# prototype2.net
KiCad netlist of a schematic drawn in EAGLE
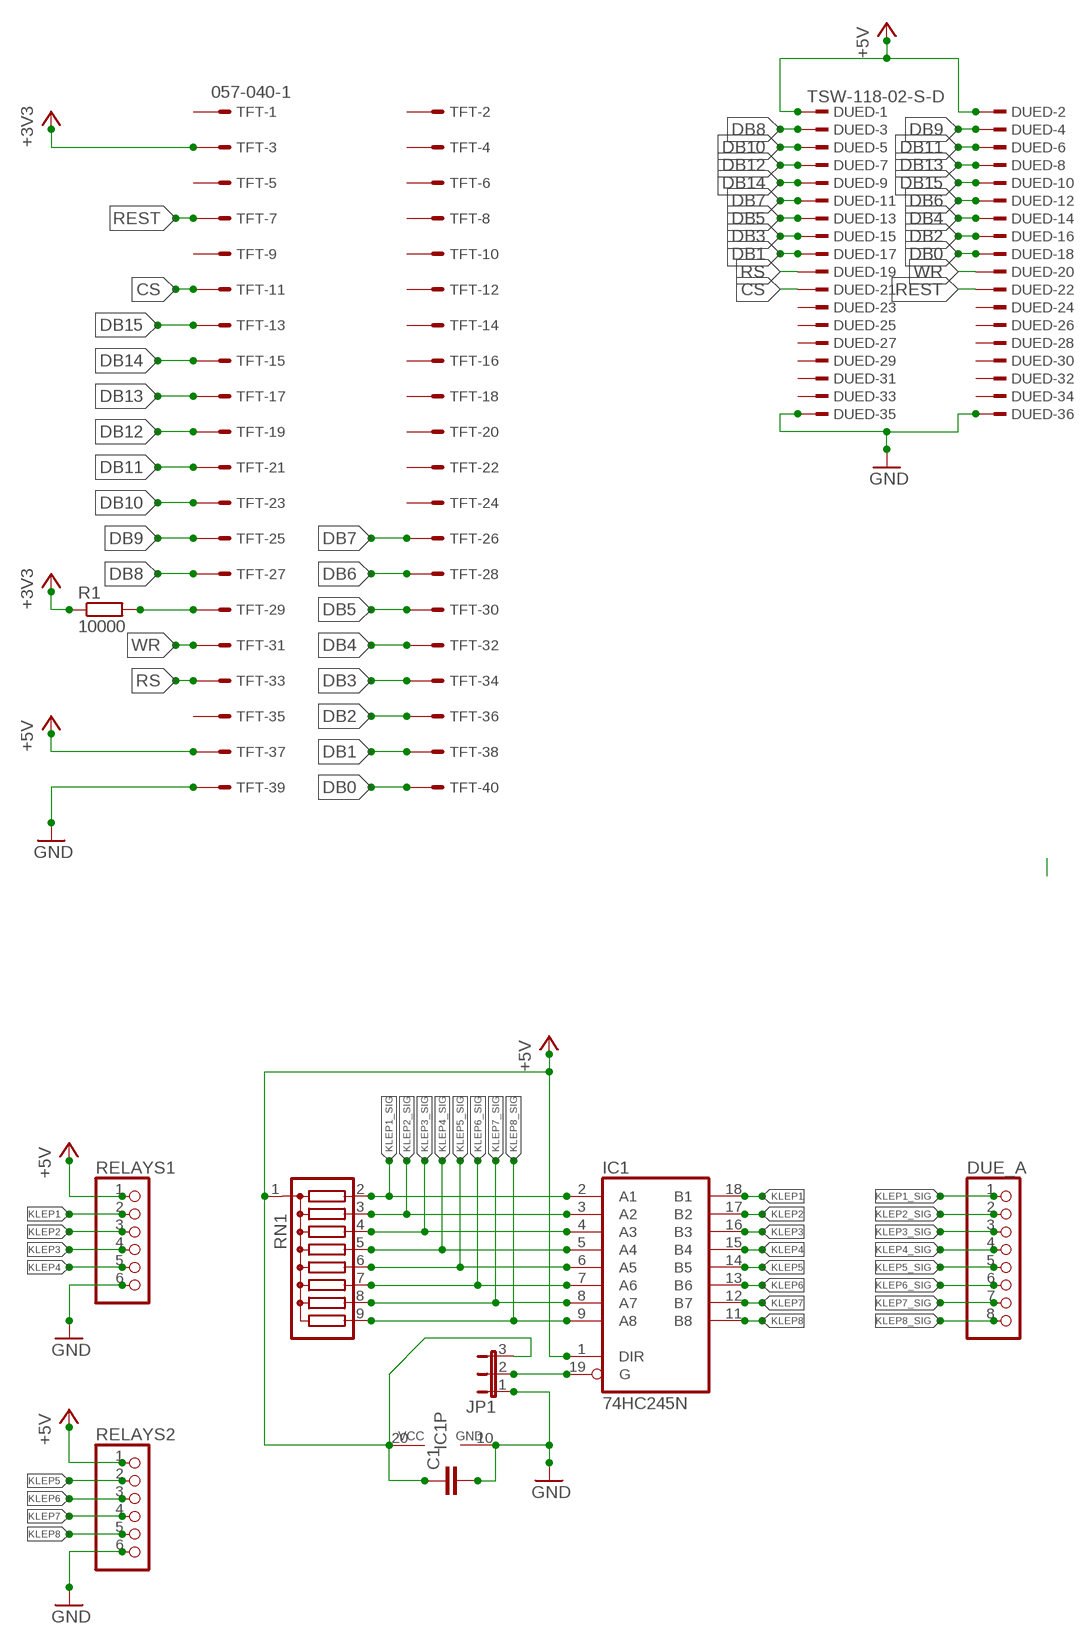
[diagram p0: schematic, sheet 1, part 1 of 2]
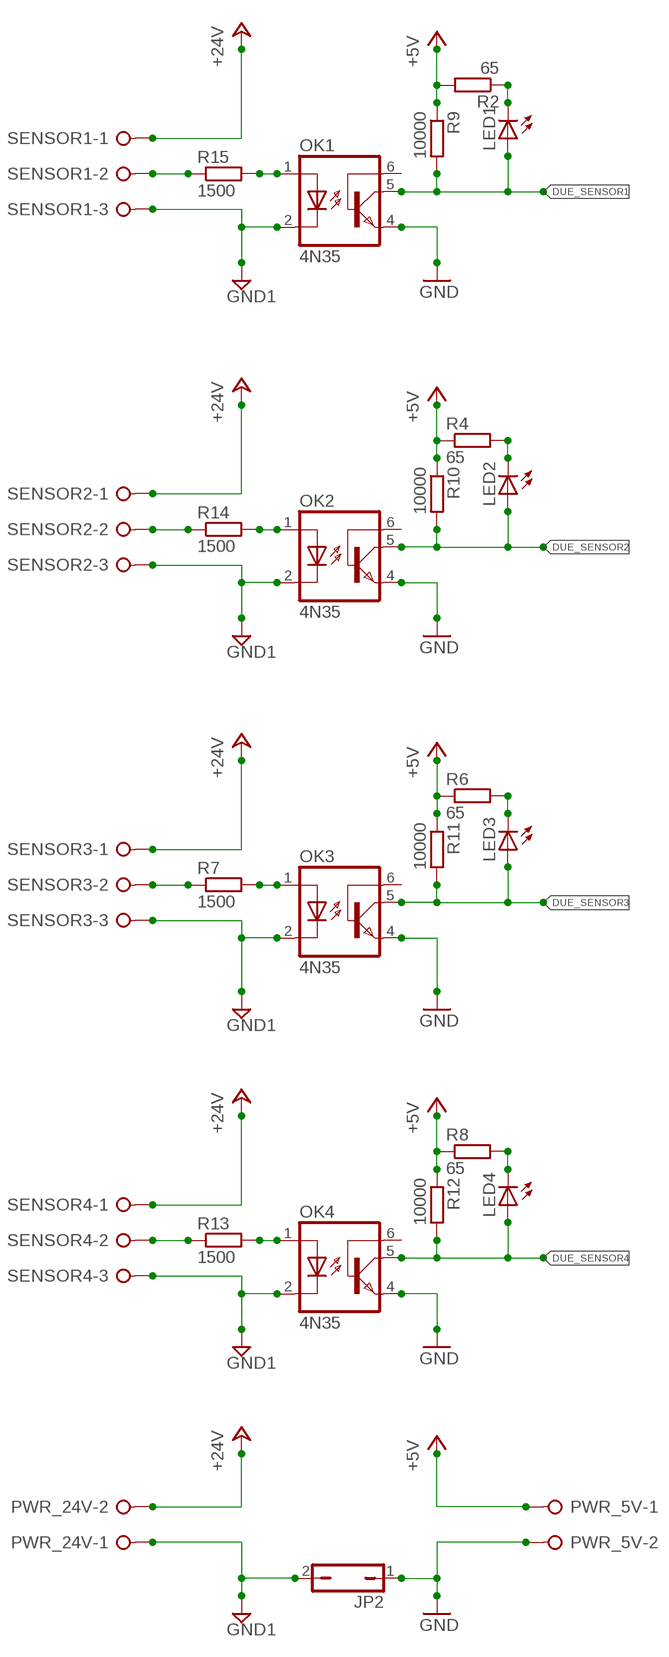
[diagram p1: schematic, sheet 1, part 2 of 2]

(export (version "E")
  (design (tool "Eeschema 10.0.6"))
  (components
    (comp (ref "C1")
      (value "C-EU025-024X044")
      (footprint "eagle-import:C025-024X044")
      (libsource (lib "eagle-import") (part "C-EU025-024X044"))
    )
    (comp (ref "DUED")
      (value "TSW-118-02-S-D")
      (footprint "eagle-import:TSW-118-02-S-D")
      (libsource (lib "eagle-import") (part "TSW-118-02-S-D"))
    )
    (comp (ref "DUE_A")
      (value "PINHD-1X8")
      (footprint "eagle-import:1X08")
      (libsource (lib "eagle-import") (part "PINHD-1X8"))
    )
    (comp (ref "IC1")
      (value "74HC245N")
      (footprint "eagle-import:DIL20")
      (libsource (lib "eagle-import") (part "74245NHC"))
    )
    (comp (ref "JP1")
      (value "JP2E")
      (footprint "eagle-import:JP2")
      (libsource (lib "eagle-import") (part "JP2E"))
    )
    (comp (ref "JP2")
      (value "JP1Q")
      (footprint "eagle-import:JP1")
      (libsource (lib "eagle-import") (part "JP1Q"))
    )
    (comp (ref "LED1")
      (value "LED5MM")
      (footprint "eagle-import:LED5MM")
      (libsource (lib "eagle-import") (part "LED5MM"))
    )
    (comp (ref "LED2")
      (value "LED5MM")
      (footprint "eagle-import:LED5MM")
      (libsource (lib "eagle-import") (part "LED5MM"))
    )
    (comp (ref "LED3")
      (value "LED5MM")
      (footprint "eagle-import:LED5MM")
      (libsource (lib "eagle-import") (part "LED5MM"))
    )
    (comp (ref "LED4")
      (value "LED5MM")
      (footprint "eagle-import:LED5MM")
      (libsource (lib "eagle-import") (part "LED5MM"))
    )
    (comp (ref "OK1")
      (value "4N35")
      (footprint "eagle-import:DIL06")
      (fields (field (name "MF") "FAIRCHILD SEMICONDUCTOR"))
      (libsource (lib "eagle-import") (part "4N35"))
    )
    (comp (ref "OK2")
      (value "4N35")
      (footprint "eagle-import:DIL06")
      (fields (field (name "MF") "FAIRCHILD SEMICONDUCTOR"))
      (libsource (lib "eagle-import") (part "4N35"))
    )
    (comp (ref "OK3")
      (value "4N35")
      (footprint "eagle-import:DIL06")
      (fields (field (name "MF") "FAIRCHILD SEMICONDUCTOR"))
      (libsource (lib "eagle-import") (part "4N35"))
    )
    (comp (ref "OK4")
      (value "4N35")
      (footprint "eagle-import:DIL06")
      (fields (field (name "MF") "FAIRCHILD SEMICONDUCTOR"))
      (libsource (lib "eagle-import") (part "4N35"))
    )
    (comp (ref "PWR_5V")
      (value "W237-02P")
      (footprint "eagle-import:W237-132")
      (libsource (lib "eagle-import") (part "W237-02P"))
    )
    (comp (ref "PWR_24V")
      (value "W237-02P")
      (footprint "eagle-import:W237-132")
      (libsource (lib "eagle-import") (part "W237-02P"))
    )
    (comp (ref "R1")
      (value "10000")
      (footprint "eagle-import:0204_5")
      (libsource (lib "eagle-import") (part "R-EU_0204/5"))
    )
    (comp (ref "R2")
      (value "65")
      (footprint "eagle-import:0204_5")
      (libsource (lib "eagle-import") (part "R-EU_0204/5"))
    )
    (comp (ref "R4")
      (value "65")
      (footprint "eagle-import:0204_5")
      (libsource (lib "eagle-import") (part "R-EU_0204/5"))
    )
    (comp (ref "R6")
      (value "65")
      (footprint "eagle-import:0204_5")
      (libsource (lib "eagle-import") (part "R-EU_0204/5"))
    )
    (comp (ref "R7")
      (value "1500")
      (footprint "eagle-import:0204_5")
      (libsource (lib "eagle-import") (part "R-EU_0204/5"))
    )
    (comp (ref "R8")
      (value "65")
      (footprint "eagle-import:0204_5")
      (libsource (lib "eagle-import") (part "R-EU_0204/5"))
    )
    (comp (ref "R9")
      (value "10000")
      (footprint "eagle-import:0204_5")
      (libsource (lib "eagle-import") (part "R-EU_0204/5"))
    )
    (comp (ref "R10")
      (value "10000")
      (footprint "eagle-import:0204_5")
      (libsource (lib "eagle-import") (part "R-EU_0204/5"))
    )
    (comp (ref "R11")
      (value "10000")
      (footprint "eagle-import:0204_5")
      (libsource (lib "eagle-import") (part "R-EU_0204/5"))
    )
    (comp (ref "R12")
      (value "10000")
      (footprint "eagle-import:0204_5")
      (libsource (lib "eagle-import") (part "R-EU_0204/5"))
    )
    (comp (ref "R13")
      (value "1500")
      (footprint "eagle-import:0204_5")
      (libsource (lib "eagle-import") (part "R-EU_0204/5"))
    )
    (comp (ref "R14")
      (value "1500")
      (footprint "eagle-import:0204_5")
      (libsource (lib "eagle-import") (part "R-EU_0204/5"))
    )
    (comp (ref "R15")
      (value "1500")
      (footprint "eagle-import:0204_5")
      (libsource (lib "eagle-import") (part "R-EU_0204/5"))
    )
    (comp (ref "RELAYS1")
      (value "PINHD-1X6")
      (footprint "eagle-import:1X06")
      (libsource (lib "eagle-import") (part "PINHD-1X6"))
    )
    (comp (ref "RELAYS2")
      (value "PINHD-1X6")
      (footprint "eagle-import:1X06")
      (libsource (lib "eagle-import") (part "PINHD-1X6"))
    )
    (comp (ref "RN1")
      (value "G08R")
      (footprint "eagle-import:SIL9")
      (libsource (lib "eagle-import") (part "G08R"))
    )
    (comp (ref "SENSOR1")
      (value "W237-03P")
      (footprint "eagle-import:W237-133")
      (libsource (lib "eagle-import") (part "W237-03P"))
    )
    (comp (ref "SENSOR2")
      (value "W237-03P")
      (footprint "eagle-import:W237-133")
      (libsource (lib "eagle-import") (part "W237-03P"))
    )
    (comp (ref "SENSOR3")
      (value "W237-03P")
      (footprint "eagle-import:W237-133")
      (libsource (lib "eagle-import") (part "W237-03P"))
    )
    (comp (ref "SENSOR4")
      (value "W237-03P")
      (footprint "eagle-import:W237-133")
      (libsource (lib "eagle-import") (part "W237-03P"))
    )
    (comp (ref "TFT")
      (value "057-040-1")
      (footprint "eagle-import:057-040-1")
      (libsource (lib "eagle-import") (part "057-040-1"))
    )
  )
  (nets
    (net (code "1") (name "+3V3") (class "Default")
      (node (ref "R1") (pin "1") (pinfunction "1_1") (pintype "passive"))
      (node (ref "TFT") (pin "3") (pinfunction "S_3") (pintype "passive"))
    )
    (net (code "2") (name "+5V") (class "Default")
      (node (ref "C1") (pin "1") (pinfunction "1_1") (pintype "passive"))
      (node (ref "DUED") (pin "1") (pinfunction "1_1") (pintype "passive"))
      (node (ref "DUED") (pin "2") (pinfunction "1_2") (pintype "passive"))
      (node (ref "IC1") (pin "1") (pinfunction "DIR_1") (pintype "input"))
      (node (ref "IC1") (pin "20") (pinfunction "VCC_20") (pintype "power_in"))
      (node (ref "JP1") (pin "3") (pinfunction "3_3") (pintype "passive"))
      (node (ref "PWR_5V") (pin "1") (pinfunction "KL_1") (pintype "passive"))
      (node (ref "R10") (pin "1") (pinfunction "1_1") (pintype "passive"))
      (node (ref "R11") (pin "1") (pinfunction "1_1") (pintype "passive"))
      (node (ref "R12") (pin "1") (pinfunction "1_1") (pintype "passive"))
      (node (ref "R2") (pin "2") (pinfunction "2_2") (pintype "passive"))
      (node (ref "R4") (pin "1") (pinfunction "1_1") (pintype "passive"))
      (node (ref "R6") (pin "1") (pinfunction "1_1") (pintype "passive"))
      (node (ref "R8") (pin "1") (pinfunction "1_1") (pintype "passive"))
      (node (ref "R9") (pin "1") (pinfunction "1_1") (pintype "passive"))
      (node (ref "RELAYS1") (pin "1") (pinfunction "1_1") (pintype "passive"))
      (node (ref "RELAYS2") (pin "1") (pinfunction "1_1") (pintype "passive"))
      (node (ref "RN1") (pin "1") (pinfunction "1_1") (pintype "passive"))
      (node (ref "TFT") (pin "37") (pinfunction "S_37") (pintype "passive"))
    )
    (net (code "3") (name "+24V") (class "Default")
      (node (ref "PWR_24V") (pin "2") (pinfunction "KL_2") (pintype "passive"))
      (node (ref "SENSOR1") (pin "1") (pinfunction "KL_1") (pintype "passive"))
      (node (ref "SENSOR2") (pin "1") (pinfunction "KL_1") (pintype "passive"))
      (node (ref "SENSOR3") (pin "1") (pinfunction "KL_1") (pintype "passive"))
      (node (ref "SENSOR4") (pin "1") (pinfunction "KL_1") (pintype "passive"))
    )
    (net (code "4") (name "CS") (class "Default")
      (node (ref "DUED") (pin "21") (pinfunction "1_21") (pintype "passive"))
      (node (ref "TFT") (pin "11") (pinfunction "S_11") (pintype "passive"))
    )
    (net (code "5") (name "DB0") (class "Default")
      (node (ref "DUED") (pin "18") (pinfunction "1_18") (pintype "passive"))
      (node (ref "TFT") (pin "40") (pinfunction "S_40") (pintype "passive"))
    )
    (net (code "6") (name "DB1") (class "Default")
      (node (ref "DUED") (pin "17") (pinfunction "1_17") (pintype "passive"))
      (node (ref "TFT") (pin "38") (pinfunction "S_38") (pintype "passive"))
    )
    (net (code "7") (name "DB2") (class "Default")
      (node (ref "DUED") (pin "16") (pinfunction "1_16") (pintype "passive"))
      (node (ref "TFT") (pin "36") (pinfunction "S_36") (pintype "passive"))
    )
    (net (code "8") (name "DB3") (class "Default")
      (node (ref "DUED") (pin "15") (pinfunction "1_15") (pintype "passive"))
      (node (ref "TFT") (pin "34") (pinfunction "S_34") (pintype "passive"))
    )
    (net (code "9") (name "DB4") (class "Default")
      (node (ref "DUED") (pin "14") (pinfunction "1_14") (pintype "passive"))
      (node (ref "TFT") (pin "32") (pinfunction "S_32") (pintype "passive"))
    )
    (net (code "10") (name "DB5") (class "Default")
      (node (ref "DUED") (pin "13") (pinfunction "1_13") (pintype "passive"))
      (node (ref "TFT") (pin "30") (pinfunction "S_30") (pintype "passive"))
    )
    (net (code "11") (name "DB6") (class "Default")
      (node (ref "DUED") (pin "12") (pinfunction "1_12") (pintype "passive"))
      (node (ref "TFT") (pin "28") (pinfunction "S_28") (pintype "passive"))
    )
    (net (code "12") (name "DB7") (class "Default")
      (node (ref "DUED") (pin "11") (pinfunction "1_11") (pintype "passive"))
      (node (ref "TFT") (pin "26") (pinfunction "S_26") (pintype "passive"))
    )
    (net (code "13") (name "DB8") (class "Default")
      (node (ref "DUED") (pin "3") (pinfunction "1_3") (pintype "passive"))
      (node (ref "TFT") (pin "27") (pinfunction "S_27") (pintype "passive"))
    )
    (net (code "14") (name "DB9") (class "Default")
      (node (ref "DUED") (pin "4") (pinfunction "1_4") (pintype "passive"))
      (node (ref "TFT") (pin "25") (pinfunction "S_25") (pintype "passive"))
    )
    (net (code "15") (name "DB10") (class "Default")
      (node (ref "DUED") (pin "5") (pinfunction "1_5") (pintype "passive"))
      (node (ref "TFT") (pin "23") (pinfunction "S_23") (pintype "passive"))
    )
    (net (code "16") (name "DB11") (class "Default")
      (node (ref "DUED") (pin "6") (pinfunction "1_6") (pintype "passive"))
      (node (ref "TFT") (pin "21") (pinfunction "S_21") (pintype "passive"))
    )
    (net (code "17") (name "DB12") (class "Default")
      (node (ref "DUED") (pin "7") (pinfunction "1_7") (pintype "passive"))
      (node (ref "TFT") (pin "19") (pinfunction "S_19") (pintype "passive"))
    )
    (net (code "18") (name "DB13") (class "Default")
      (node (ref "DUED") (pin "8") (pinfunction "1_8") (pintype "passive"))
      (node (ref "TFT") (pin "17") (pinfunction "S_17") (pintype "passive"))
    )
    (net (code "19") (name "DB14") (class "Default")
      (node (ref "DUED") (pin "9") (pinfunction "1_9") (pintype "passive"))
      (node (ref "TFT") (pin "15") (pinfunction "S_15") (pintype "passive"))
    )
    (net (code "20") (name "DB15") (class "Default")
      (node (ref "DUED") (pin "10") (pinfunction "1_10") (pintype "passive"))
      (node (ref "TFT") (pin "13") (pinfunction "S_13") (pintype "passive"))
    )
    (net (code "21") (name "DUE_SENSOR1") (class "Default")
      (node (ref "LED1") (pin "A") (pinfunction "A_A") (pintype "passive"))
      (node (ref "OK1") (pin "5") (pinfunction "COL_5") (pintype "passive"))
      (node (ref "R9") (pin "2") (pinfunction "2_2") (pintype "passive"))
    )
    (net (code "22") (name "DUE_SENSOR2") (class "Default")
      (node (ref "LED2") (pin "A") (pinfunction "A_A") (pintype "passive"))
      (node (ref "OK2") (pin "5") (pinfunction "COL_5") (pintype "passive"))
      (node (ref "R10") (pin "2") (pinfunction "2_2") (pintype "passive"))
    )
    (net (code "23") (name "DUE_SENSOR3") (class "Default")
      (node (ref "LED3") (pin "A") (pinfunction "A_A") (pintype "passive"))
      (node (ref "OK3") (pin "5") (pinfunction "COL_5") (pintype "passive"))
      (node (ref "R11") (pin "2") (pinfunction "2_2") (pintype "passive"))
    )
    (net (code "24") (name "DUE_SENSOR4") (class "Default")
      (node (ref "LED4") (pin "A") (pinfunction "A_A") (pintype "passive"))
      (node (ref "OK4") (pin "5") (pinfunction "COL_5") (pintype "passive"))
      (node (ref "R12") (pin "2") (pinfunction "2_2") (pintype "passive"))
    )
    (net (code "25") (name "GND") (class "Default")
      (node (ref "C1") (pin "2") (pinfunction "2_2") (pintype "passive"))
      (node (ref "DUED") (pin "35") (pinfunction "1_35") (pintype "passive"))
      (node (ref "DUED") (pin "36") (pinfunction "1_36") (pintype "passive"))
      (node (ref "IC1") (pin "10") (pinfunction "GND_10") (pintype "power_in"))
      (node (ref "JP1") (pin "1") (pinfunction "1_1") (pintype "passive"))
      (node (ref "JP2") (pin "1") (pinfunction "1_1") (pintype "passive"))
      (node (ref "OK1") (pin "4") (pinfunction "EMI_4") (pintype "passive"))
      (node (ref "OK2") (pin "4") (pinfunction "EMI_4") (pintype "passive"))
      (node (ref "OK3") (pin "4") (pinfunction "EMI_4") (pintype "passive"))
      (node (ref "OK4") (pin "4") (pinfunction "EMI_4") (pintype "passive"))
      (node (ref "PWR_5V") (pin "2") (pinfunction "KL_2") (pintype "passive"))
      (node (ref "RELAYS1") (pin "6") (pinfunction "6_6") (pintype "passive"))
      (node (ref "RELAYS2") (pin "6") (pinfunction "6_6") (pintype "passive"))
      (node (ref "TFT") (pin "39") (pinfunction "S_39") (pintype "passive"))
    )
    (net (code "26") (name "GND1") (class "Default")
      (node (ref "JP2") (pin "2") (pinfunction "2_2") (pintype "passive"))
      (node (ref "OK1") (pin "2") (pinfunction "C_2") (pintype "passive"))
      (node (ref "OK2") (pin "2") (pinfunction "C_2") (pintype "passive"))
      (node (ref "OK3") (pin "2") (pinfunction "C_2") (pintype "passive"))
      (node (ref "OK4") (pin "2") (pinfunction "C_2") (pintype "passive"))
      (node (ref "PWR_24V") (pin "1") (pinfunction "KL_1") (pintype "passive"))
      (node (ref "SENSOR1") (pin "3") (pinfunction "KL_3") (pintype "passive"))
      (node (ref "SENSOR2") (pin "3") (pinfunction "KL_3") (pintype "passive"))
      (node (ref "SENSOR3") (pin "3") (pinfunction "KL_3") (pintype "passive"))
      (node (ref "SENSOR4") (pin "3") (pinfunction "KL_3") (pintype "passive"))
    )
    (net (code "27") (name "KLEP1") (class "Default")
      (node (ref "IC1") (pin "18") (pinfunction "B1_18") (pintype "bidirectional"))
      (node (ref "RELAYS1") (pin "2") (pinfunction "2_2") (pintype "passive"))
    )
    (net (code "28") (name "KLEP1_SIG") (class "Default")
      (node (ref "DUE_A") (pin "1") (pinfunction "1_1") (pintype "passive"))
      (node (ref "IC1") (pin "2") (pinfunction "A1_2") (pintype "bidirectional"))
      (node (ref "RN1") (pin "2") (pinfunction "2_2") (pintype "passive"))
    )
    (net (code "29") (name "KLEP2") (class "Default")
      (node (ref "IC1") (pin "17") (pinfunction "B2_17") (pintype "bidirectional"))
      (node (ref "RELAYS1") (pin "3") (pinfunction "3_3") (pintype "passive"))
    )
    (net (code "30") (name "KLEP2_SIG") (class "Default")
      (node (ref "DUE_A") (pin "2") (pinfunction "2_2") (pintype "passive"))
      (node (ref "IC1") (pin "3") (pinfunction "A2_3") (pintype "bidirectional"))
      (node (ref "RN1") (pin "3") (pinfunction "3_3") (pintype "passive"))
    )
    (net (code "31") (name "KLEP3") (class "Default")
      (node (ref "IC1") (pin "16") (pinfunction "B3_16") (pintype "bidirectional"))
      (node (ref "RELAYS1") (pin "4") (pinfunction "4_4") (pintype "passive"))
    )
    (net (code "32") (name "KLEP3_SIG") (class "Default")
      (node (ref "DUE_A") (pin "3") (pinfunction "3_3") (pintype "passive"))
      (node (ref "IC1") (pin "4") (pinfunction "A3_4") (pintype "bidirectional"))
      (node (ref "RN1") (pin "4") (pinfunction "4_4") (pintype "passive"))
    )
    (net (code "33") (name "KLEP4") (class "Default")
      (node (ref "IC1") (pin "15") (pinfunction "B4_15") (pintype "bidirectional"))
      (node (ref "RELAYS1") (pin "5") (pinfunction "5_5") (pintype "passive"))
    )
    (net (code "34") (name "KLEP4_SIG") (class "Default")
      (node (ref "DUE_A") (pin "4") (pinfunction "4_4") (pintype "passive"))
      (node (ref "IC1") (pin "5") (pinfunction "A4_5") (pintype "bidirectional"))
      (node (ref "RN1") (pin "5") (pinfunction "5_5") (pintype "passive"))
    )
    (net (code "35") (name "KLEP5") (class "Default")
      (node (ref "IC1") (pin "14") (pinfunction "B5_14") (pintype "bidirectional"))
      (node (ref "RELAYS2") (pin "2") (pinfunction "2_2") (pintype "passive"))
    )
    (net (code "36") (name "KLEP5_SIG") (class "Default")
      (node (ref "DUE_A") (pin "5") (pinfunction "5_5") (pintype "passive"))
      (node (ref "IC1") (pin "6") (pinfunction "A5_6") (pintype "bidirectional"))
      (node (ref "RN1") (pin "6") (pinfunction "6_6") (pintype "passive"))
    )
    (net (code "37") (name "KLEP6") (class "Default")
      (node (ref "IC1") (pin "13") (pinfunction "B6_13") (pintype "bidirectional"))
      (node (ref "RELAYS2") (pin "3") (pinfunction "3_3") (pintype "passive"))
    )
    (net (code "38") (name "KLEP6_SIG") (class "Default")
      (node (ref "DUE_A") (pin "6") (pinfunction "6_6") (pintype "passive"))
      (node (ref "IC1") (pin "7") (pinfunction "A6_7") (pintype "bidirectional"))
      (node (ref "RN1") (pin "7") (pinfunction "7_7") (pintype "passive"))
    )
    (net (code "39") (name "KLEP7") (class "Default")
      (node (ref "IC1") (pin "12") (pinfunction "B7_12") (pintype "bidirectional"))
      (node (ref "RELAYS2") (pin "4") (pinfunction "4_4") (pintype "passive"))
    )
    (net (code "40") (name "KLEP7_SIG") (class "Default")
      (node (ref "DUE_A") (pin "7") (pinfunction "7_7") (pintype "passive"))
      (node (ref "IC1") (pin "8") (pinfunction "A7_8") (pintype "bidirectional"))
      (node (ref "RN1") (pin "8") (pinfunction "8_8") (pintype "passive"))
    )
    (net (code "41") (name "KLEP8") (class "Default")
      (node (ref "IC1") (pin "11") (pinfunction "B8_11") (pintype "bidirectional"))
      (node (ref "RELAYS2") (pin "5") (pinfunction "5_5") (pintype "passive"))
    )
    (net (code "42") (name "KLEP8_SIG") (class "Default")
      (node (ref "DUE_A") (pin "8") (pinfunction "8_8") (pintype "passive"))
      (node (ref "IC1") (pin "9") (pinfunction "A8_9") (pintype "bidirectional"))
      (node (ref "RN1") (pin "9") (pinfunction "9_9") (pintype "passive"))
    )
    (net (code "43") (name "Net-(IC1A-G)") (class "Default")
      (node (ref "IC1") (pin "19") (pinfunction "G_19") (pintype "input"))
      (node (ref "JP1") (pin "2") (pinfunction "2_2") (pintype "passive"))
    )
    (net (code "44") (name "Net-(LED1-C)") (class "Default")
      (node (ref "LED1") (pin "K") (pinfunction "C_K") (pintype "passive"))
      (node (ref "R2") (pin "1") (pinfunction "1_1") (pintype "passive"))
    )
    (net (code "45") (name "Net-(LED2-C)") (class "Default")
      (node (ref "LED2") (pin "K") (pinfunction "C_K") (pintype "passive"))
      (node (ref "R4") (pin "2") (pinfunction "2_2") (pintype "passive"))
    )
    (net (code "46") (name "Net-(LED3-C)") (class "Default")
      (node (ref "LED3") (pin "K") (pinfunction "C_K") (pintype "passive"))
      (node (ref "R6") (pin "2") (pinfunction "2_2") (pintype "passive"))
    )
    (net (code "47") (name "Net-(LED4-C)") (class "Default")
      (node (ref "LED4") (pin "K") (pinfunction "C_K") (pintype "passive"))
      (node (ref "R8") (pin "2") (pinfunction "2_2") (pintype "passive"))
    )
    (net (code "48") (name "Net-(OK1-A)") (class "Default")
      (node (ref "OK1") (pin "1") (pinfunction "A_1") (pintype "passive"))
      (node (ref "R15") (pin "2") (pinfunction "2_2") (pintype "passive"))
    )
    (net (code "49") (name "Net-(OK2-A)") (class "Default")
      (node (ref "OK2") (pin "1") (pinfunction "A_1") (pintype "passive"))
      (node (ref "R14") (pin "2") (pinfunction "2_2") (pintype "passive"))
    )
    (net (code "50") (name "Net-(OK3-A)") (class "Default")
      (node (ref "OK3") (pin "1") (pinfunction "A_1") (pintype "passive"))
      (node (ref "R7") (pin "2") (pinfunction "2_2") (pintype "passive"))
    )
    (net (code "51") (name "Net-(OK4-A)") (class "Default")
      (node (ref "OK4") (pin "1") (pinfunction "A_1") (pintype "passive"))
      (node (ref "R13") (pin "2") (pinfunction "2_2") (pintype "passive"))
    )
    (net (code "52") (name "Net-(SENSOR1B-KL)") (class "Default")
      (node (ref "R15") (pin "1") (pinfunction "1_1") (pintype "passive"))
      (node (ref "SENSOR1") (pin "2") (pinfunction "KL_2") (pintype "passive"))
    )
    (net (code "53") (name "Net-(SENSOR2B-KL)") (class "Default")
      (node (ref "R14") (pin "1") (pinfunction "1_1") (pintype "passive"))
      (node (ref "SENSOR2") (pin "2") (pinfunction "KL_2") (pintype "passive"))
    )
    (net (code "54") (name "Net-(SENSOR3B-KL)") (class "Default")
      (node (ref "R7") (pin "1") (pinfunction "1_1") (pintype "passive"))
      (node (ref "SENSOR3") (pin "2") (pinfunction "KL_2") (pintype "passive"))
    )
    (net (code "55") (name "Net-(SENSOR4B-KL)") (class "Default")
      (node (ref "R13") (pin "1") (pinfunction "1_1") (pintype "passive"))
      (node (ref "SENSOR4") (pin "2") (pinfunction "KL_2") (pintype "passive"))
    )
    (net (code "56") (name "Net-(TFTV-S)") (class "Default")
      (node (ref "R1") (pin "2") (pinfunction "2_2") (pintype "passive"))
      (node (ref "TFT") (pin "29") (pinfunction "S_29") (pintype "passive"))
    )
    (net (code "57") (name "REST") (class "Default")
      (node (ref "DUED") (pin "22") (pinfunction "1_22") (pintype "passive"))
      (node (ref "TFT") (pin "7") (pinfunction "S_7") (pintype "passive"))
    )
    (net (code "58") (name "RS") (class "Default")
      (node (ref "DUED") (pin "19") (pinfunction "1_19") (pintype "passive"))
      (node (ref "TFT") (pin "33") (pinfunction "S_33") (pintype "passive"))
    )
    (net (code "59") (name "WR") (class "Default")
      (node (ref "DUED") (pin "20") (pinfunction "1_20") (pintype "passive"))
      (node (ref "TFT") (pin "31") (pinfunction "S_31") (pintype "passive"))
    )
    (net (code "60") (name "unconnected-(DUEDAA-1-Pad33)") (class "Default")
      (node (ref "DUED") (pin "33") (pinfunction "1_33") (pintype "passive"))
    )
    (net (code "61") (name "unconnected-(DUEDAB-1-Pad34)") (class "Default")
      (node (ref "DUED") (pin "34") (pinfunction "1_34") (pintype "passive"))
    )
    (net (code "62") (name "unconnected-(DUEDP-1-Pad23)") (class "Default")
      (node (ref "DUED") (pin "23") (pinfunction "1_23") (pintype "passive"))
    )
    (net (code "63") (name "unconnected-(DUEDQ-1-Pad24)") (class "Default")
      (node (ref "DUED") (pin "24") (pinfunction "1_24") (pintype "passive"))
    )
    (net (code "64") (name "unconnected-(DUEDR-1-Pad25)") (class "Default")
      (node (ref "DUED") (pin "25") (pinfunction "1_25") (pintype "passive"))
    )
    (net (code "65") (name "unconnected-(DUEDS-1-Pad26)") (class "Default")
      (node (ref "DUED") (pin "26") (pinfunction "1_26") (pintype "passive"))
    )
    (net (code "66") (name "unconnected-(DUEDT-1-Pad27)") (class "Default")
      (node (ref "DUED") (pin "27") (pinfunction "1_27") (pintype "passive"))
    )
    (net (code "67") (name "unconnected-(DUEDU-1-Pad28)") (class "Default")
      (node (ref "DUED") (pin "28") (pinfunction "1_28") (pintype "passive"))
    )
    (net (code "68") (name "unconnected-(DUEDV-1-Pad29)") (class "Default")
      (node (ref "DUED") (pin "29") (pinfunction "1_29") (pintype "passive"))
    )
    (net (code "69") (name "unconnected-(DUEDX-1-Pad30)") (class "Default")
      (node (ref "DUED") (pin "30") (pinfunction "1_30") (pintype "passive"))
    )
    (net (code "70") (name "unconnected-(DUEDY-1-Pad31)") (class "Default")
      (node (ref "DUED") (pin "31") (pinfunction "1_31") (pintype "passive"))
    )
    (net (code "71") (name "unconnected-(DUEDZ-1-Pad32)") (class "Default")
      (node (ref "DUED") (pin "32") (pinfunction "1_32") (pintype "passive"))
    )
    (net (code "72") (name "unconnected-(OK1-BAS-Pad6)") (class "Default")
      (node (ref "OK1") (pin "6") (pinfunction "BAS_6") (pintype "passive"))
    )
    (net (code "73") (name "unconnected-(OK2-BAS-Pad6)") (class "Default")
      (node (ref "OK2") (pin "6") (pinfunction "BAS_6") (pintype "passive"))
    )
    (net (code "74") (name "unconnected-(OK3-BAS-Pad6)") (class "Default")
      (node (ref "OK3") (pin "6") (pinfunction "BAS_6") (pintype "passive"))
    )
    (net (code "75") (name "unconnected-(OK4-BAS-Pad6)") (class "Default")
      (node (ref "OK4") (pin "6") (pinfunction "BAS_6") (pintype "passive"))
    )
    (net (code "76") (name "unconnected-(TFTA-S-Pad1)") (class "Default")
      (node (ref "TFT") (pin "1") (pinfunction "S_1") (pintype "passive"))
    )
    (net (code "77") (name "unconnected-(TFTAC-S-Pad35)") (class "Default")
      (node (ref "TFT") (pin "35") (pinfunction "S_35") (pintype "passive"))
    )
    (net (code "78") (name "unconnected-(TFTAH-S-Pad4)") (class "Default")
      (node (ref "TFT") (pin "4") (pinfunction "S_4") (pintype "passive"))
    )
    (net (code "79") (name "unconnected-(TFTAJ-S-Pad5)") (class "Default")
      (node (ref "TFT") (pin "5") (pinfunction "S_5") (pintype "passive"))
    )
    (net (code "80") (name "unconnected-(TFTAK-S-Pad6)") (class "Default")
      (node (ref "TFT") (pin "6") (pinfunction "S_6") (pintype "passive"))
    )
    (net (code "81") (name "unconnected-(TFTAM-S-Pad8)") (class "Default")
      (node (ref "TFT") (pin "8") (pinfunction "S_8") (pintype "passive"))
    )
    (net (code "82") (name "unconnected-(TFTAN-S-Pad9)") (class "Default")
      (node (ref "TFT") (pin "9") (pinfunction "S_9") (pintype "passive"))
    )
    (net (code "83") (name "unconnected-(TFTB-S-Pad10)") (class "Default")
      (node (ref "TFT") (pin "10") (pinfunction "S_10") (pintype "passive"))
    )
    (net (code "84") (name "unconnected-(TFTD-S-Pad12)") (class "Default")
      (node (ref "TFT") (pin "12") (pinfunction "S_12") (pintype "passive"))
    )
    (net (code "85") (name "unconnected-(TFTF-S-Pad14)") (class "Default")
      (node (ref "TFT") (pin "14") (pinfunction "S_14") (pintype "passive"))
    )
    (net (code "86") (name "unconnected-(TFTH-S-Pad16)") (class "Default")
      (node (ref "TFT") (pin "16") (pinfunction "S_16") (pintype "passive"))
    )
    (net (code "87") (name "unconnected-(TFTJ-S-Pad18)") (class "Default")
      (node (ref "TFT") (pin "18") (pinfunction "S_18") (pintype "passive"))
    )
    (net (code "88") (name "unconnected-(TFTL-S-Pad2)") (class "Default")
      (node (ref "TFT") (pin "2") (pinfunction "S_2") (pintype "passive"))
    )
    (net (code "89") (name "unconnected-(TFTM-S-Pad20)") (class "Default")
      (node (ref "TFT") (pin "20") (pinfunction "S_20") (pintype "passive"))
    )
    (net (code "90") (name "unconnected-(TFTO-S-Pad22)") (class "Default")
      (node (ref "TFT") (pin "22") (pinfunction "S_22") (pintype "passive"))
    )
    (net (code "91") (name "unconnected-(TFTQ-S-Pad24)") (class "Default")
      (node (ref "TFT") (pin "24") (pinfunction "S_24") (pintype "passive"))
    )
  )
)
